# MC9S12C.net
KiCad netlist of a schematic drawn in Altium Designer
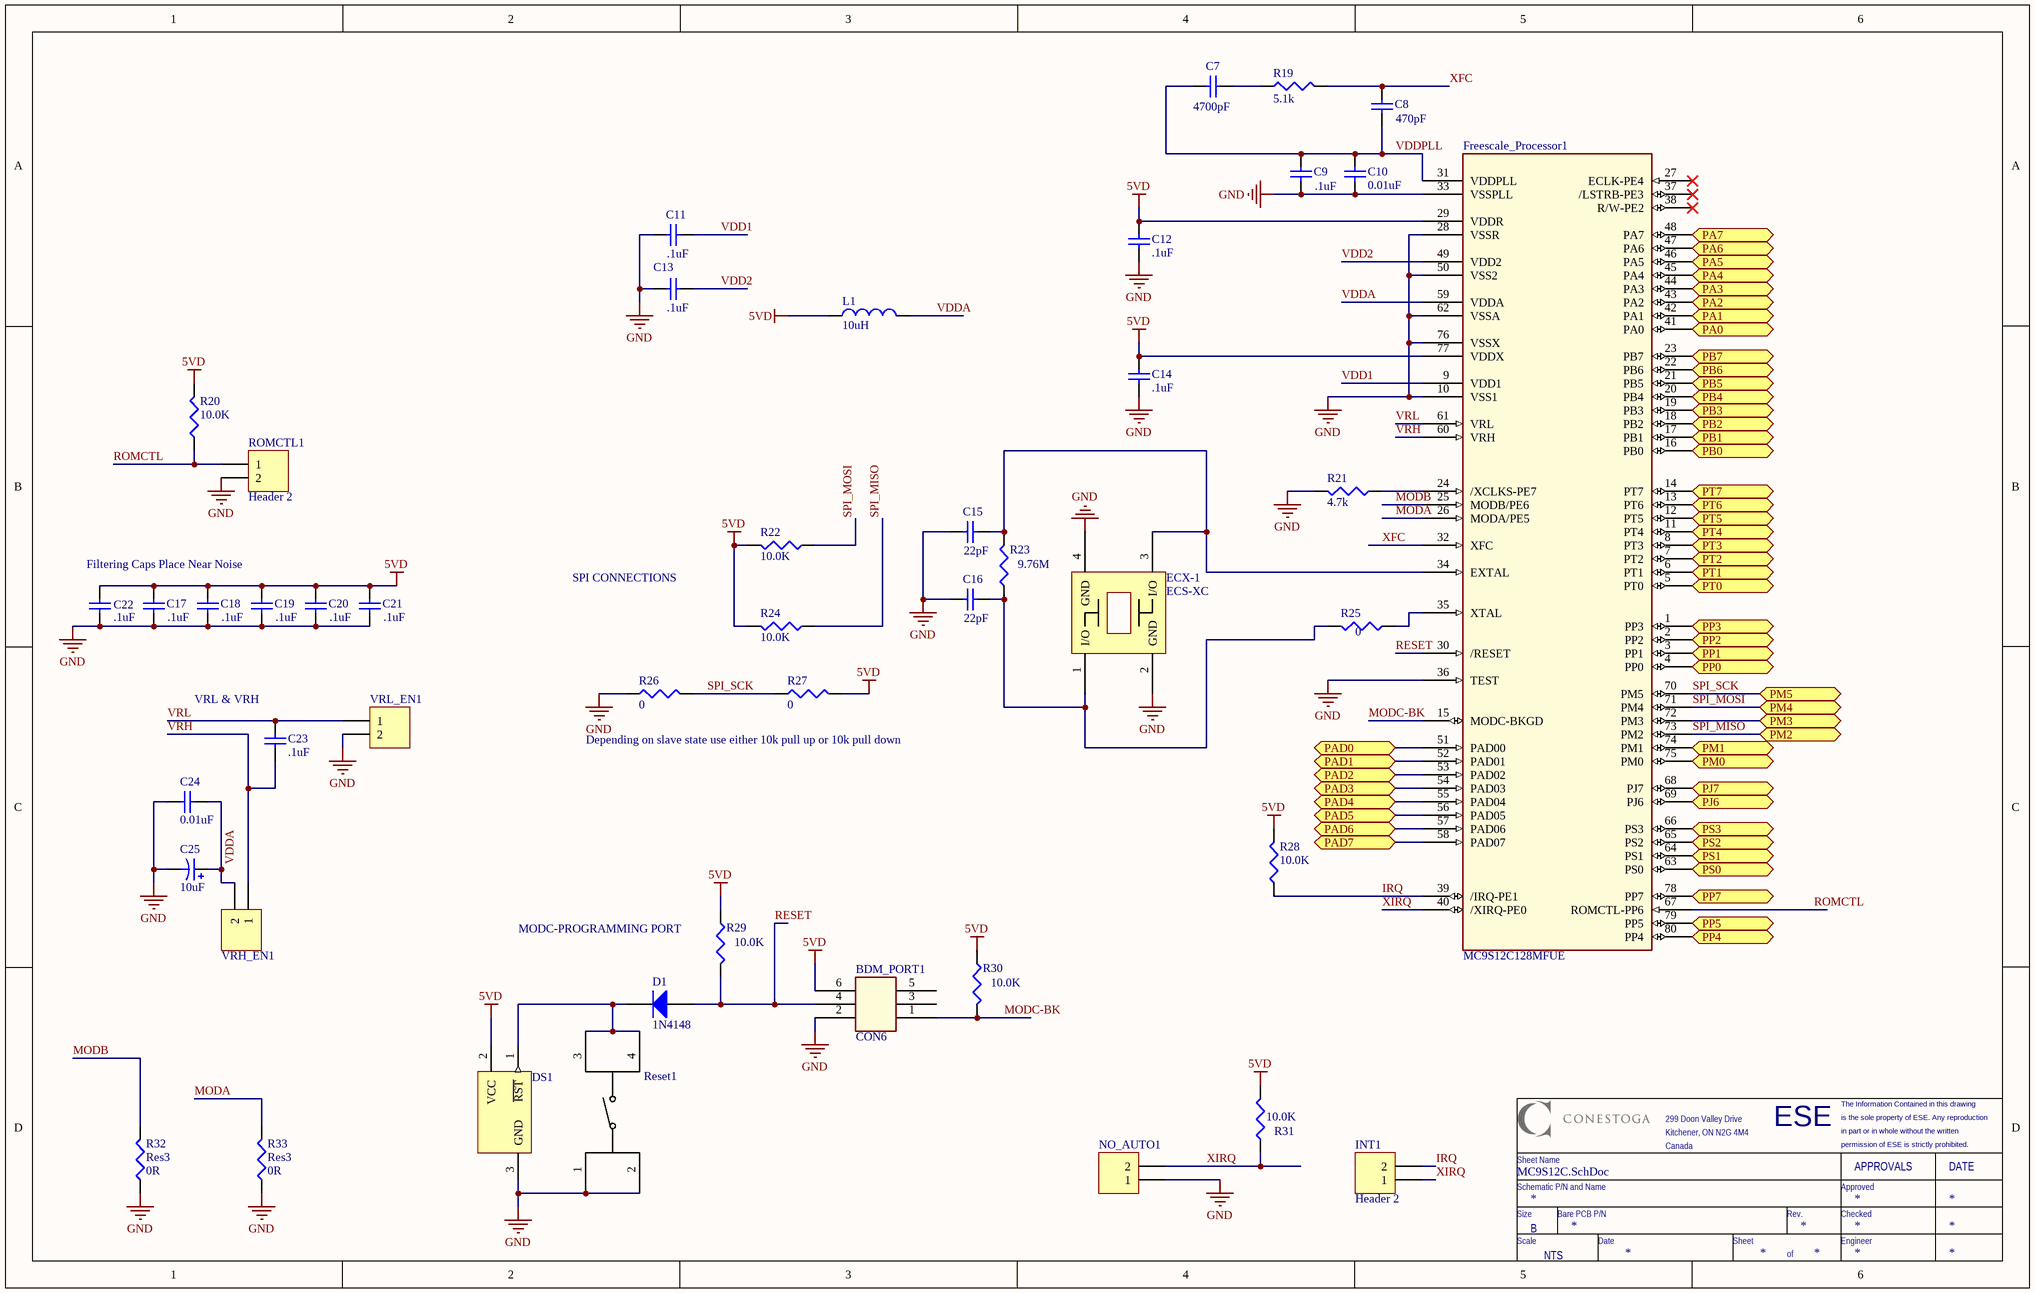
[diagram p0: MC9S12C.SchDoc]

(export (version "E")
  (design (tool "Eeschema 10.0.6"))
  (components
    (comp (ref "BDM_PORT1")
      (value "CON6")
      (footprint "HDR3X2")
      (description "CONN HEADER BRKWAY 6POS DL .100")
      (fields (field (name "MPN") "5-146254-3"))
      (libsource (lib "esd_library") (part "CON6"))
    )
    (comp (ref "C7")
      (value "4700pF")
      (footprint "CAPC2012X09M")
      (description "CAP CER 4700pF 50v X7R 0805")
      (fields (field (name "MPN") "C0805C472K5RACTU") (field (name "Comment") "p"))
      (libsource (lib "esd_library") (part "CAP-X7R-4700pF-50V-±10%"))
    )
    (comp (ref "C8")
      (value "470pF")
      (footprint "CAPC2012X09M")
      (description "CAP CER 470pF 50v X7R 0805")
      (fields (field (name "MPN") "C0805C471K5RACTU") (field (name "Comment") "ap"))
      (libsource (lib "esd_library") (part "CAP-X7R-470pF-50V-±10%"))
    )
    (comp (ref "C9")
      (value ".1uF")
      (footprint "CAPC2012X09M")
      (description "CAP CER .1uF 16v X7R 0805")
      (fields (field (name "MPN") "C0805C104K4RACTU") (field (name "Comment") "p"))
      (libsource (lib "esd_library") (part "CAP-X7R-.1uF-16V-±10%"))
    )
    (comp (ref "C10")
      (value "0.01uF")
      (footprint "C_805")
      (description "CAP CER 10000pF 50v Z5U 0805")
      (fields (field (name "MPN") "C0805C103Z5UACTU") (field (name "Comment") "Cap"))
      (libsource (lib "esd_library") (part "CAP-Z5U-10000pF-50V-+80%/-20%"))
    )
    (comp (ref "C11")
      (value ".1uF")
      (footprint "CAPC2012X09M")
      (description "CAP CER .1uF 16v X7R 0805")
      (fields (field (name "MPN") "C0805C104K4RACTU") (field (name "Comment") "Cap"))
      (libsource (lib "esd_library") (part "CAP-X7R-.1uF-16V-±10%"))
    )
    (comp (ref "C12")
      (value ".1uF")
      (footprint "C1206")
      (description "CAP CER .1uF 16v X7R 0805")
      (fields (field (name "MPN") "C0805C104K4RACTU") (field (name "Comment") "Cap"))
      (libsource (lib "esd_library") (part "CAP-X7R-.1uF-16V-±10%"))
    )
    (comp (ref "C13")
      (value ".1uF")
      (footprint "CAPC2012X09M")
      (description "CAP CER .1uF 16v X7R 0805")
      (fields (field (name "MPN") "C0805C104K4RACTU") (field (name "Comment") "Cap"))
      (libsource (lib "esd_library") (part "CAP-X7R-.1uF-16V-±10%"))
    )
    (comp (ref "C14")
      (value ".1uF")
      (footprint "C1206")
      (description "CAP CER .1uF 16v X7R 0805")
      (fields (field (name "MPN") "C0805C104K4RACTU") (field (name "Comment") "Cap"))
      (libsource (lib "esd_library") (part "CAP-X7R-.1uF-16V-±10%"))
    )
    (comp (ref "C15")
      (value "22pF")
      (footprint "CAPC2012X09M")
      (description "CAP CER 22pF 630v X7R 0805")
      (fields (field (name "MPN") "C0805C220KBRACTU") (field (name "Comment") "Cap"))
      (libsource (lib "esd_library") (part "CAP-X7R-22pF-630V-±10%"))
    )
    (comp (ref "C16")
      (value "22pF")
      (footprint "CAPC2012X09M")
      (description "CAP CER 22pF 630v X7R 0805")
      (fields (field (name "MPN") "C0805C220KBRACTU") (field (name "Comment") "Cap"))
      (libsource (lib "esd_library") (part "CAP-X7R-22pF-630V-±10%"))
    )
    (comp (ref "C17")
      (value ".1uF")
      (footprint "CAPC2012X09M")
      (description "CAP CER .1uF 50v X7R 0805")
      (fields (field (name "MPN") "C0805C104M5RACTU") (field (name "Comment") "Cap"))
      (libsource (lib "esd_library") (part "CAP-X7R-.1uF-50V-±20%"))
    )
    (comp (ref "C18")
      (value ".1uF")
      (footprint "CAPC2012X09M")
      (description "CAP CER .1uF 50v X7R 0805")
      (fields (field (name "MPN") "C0805C104M5RACTU") (field (name "Comment") "Cap"))
      (libsource (lib "esd_library") (part "CAP-X7R-.1uF-50V-±20%"))
    )
    (comp (ref "C19")
      (value ".1uF")
      (footprint "CAPC2012X09M")
      (description "CAP CER .1uF 50v X7R 0805")
      (fields (field (name "MPN") "C0805C104M5RACTU") (field (name "Comment") "Cap"))
      (libsource (lib "esd_library") (part "CAP-X7R-.1uF-50V-±20%"))
    )
    (comp (ref "C20")
      (value ".1uF")
      (footprint "CAPC2012X09M")
      (description "CAP CER .1uF 50v X7R 0805")
      (fields (field (name "MPN") "C0805C104M5RACTU") (field (name "Comment") "Cap"))
      (libsource (lib "esd_library") (part "CAP-X7R-.1uF-50V-±20%"))
    )
    (comp (ref "C21")
      (value ".1uF")
      (footprint "CAPC2012X09M")
      (description "CAP CER .1uF 50v X7R 0805")
      (fields (field (name "MPN") "C0805C104M5RACTU") (field (name "Comment") "Cap"))
      (libsource (lib "esd_library") (part "CAP-X7R-.1uF-50V-±20%"))
    )
    (comp (ref "C22")
      (value ".1uF")
      (footprint "CAPC2012X09M")
      (description "CAP CER .1uF 50v X7R 0805")
      (fields (field (name "MPN") "C0805C104M5RACTU") (field (name "Comment") "Cap"))
      (libsource (lib "esd_library") (part "CAP-X7R-.1uF-50V-±20%"))
    )
    (comp (ref "C23")
      (value ".1uF")
      (footprint "CAPC2012X09M")
      (description "CAP CER .1uF 16v X7R 0805")
      (fields (field (name "MPN") "C0805C104K4RACTU") (field (name "Comment") "Cap"))
      (libsource (lib "esd_library") (part "CAP-X7R-.1uF-16V-±10%"))
    )
    (comp (ref "C24")
      (value "0.01uF")
      (footprint "C_805")
      (description "CAP CER 10000pF 100v X7R 0805")
      (fields (field (name "MPN") "C0805C103K1RACTU") (field (name "Comment") "Cap"))
      (libsource (lib "esd_library") (part "CAP-X7R-10000pF-100V-±10%"))
    )
    (comp (ref "C25")
      (value "10uF")
      (footprint "CAPACITOR_3MM")
      (description "CAP 85C 10uF ±20% 16V WX Series Aluminum Electrolytic")
      (fields (field (name "MPN") "UWX1C100MCL2GB") (field (name "Comment") "Cap Pol"))
      (libsource (lib "esd_library") (part "Cap Polar-10uF-16V"))
    )
    (comp (ref "D1")
      (value "1N4148")
      (footprint "zener_sod323")
      (description "High Conductance Fast Diode")
      (fields (field (name "MPN") "1N4148WX-TP"))
      (libsource (lib "esd_library") (part "Diode 1N4148"))
    )
    (comp (ref "DS1")
      (value "DS1813-10")
      (footprint "SOT95P230X110-3M")
      (description "5V EconoReset with Pushbutton")
      (fields (field (name "MPN") "DS1813R-10+T&R") (field (name "PUBLISHER") "Altium Limited"))
      (libsource (lib "esd_library") (part "DS1813-10"))
    )
    (comp (ref "ECX-1") (value "ECS-XC") (footprint "ECX-32") (libsource (lib "Crystal") (part "ECS-XC")))
    (comp (ref "Freescale_Processor1")
      (value "MC9S12C128MFUE")
      (footprint "QUAD.65M/80/WG17.45-HCS12")
      (description "IC MCU 16BIT 128KB FLASH 80QFP")
      (fields (field (name "MPN") "MC9S12C32CFUE25"))
      (libsource (lib "esd_library") (part "MC9S12C128MFUE"))
    )
    (comp (ref "INT1")
      (value "Header 2")
      (footprint "HDR1X2")
      (description "Header, 2-Pin Male")
      (fields (field (name "MPN") "PEC02SFAN"))
      (libsource (lib "esd_library (1)") (part "Header 2"))
    )
    (comp (ref "L1")
      (value "10uH")
      (footprint "CAPC2012X09M")
      (libsource (lib "esd_library") (part "INDUCTOR"))
    )
    (comp (ref "NO_AUTO1")
      (value "Header 2")
      (footprint "HDR1X2")
      (description "Header, 2-Pin")
      (fields (field (name "MPN") "PEC02SFAN"))
      (libsource (lib "") (part "Header 2_1"))
    )
    (comp (ref "R19")
      (value "5.1k")
      (footprint "RESC2112X05M")
      (description "RES SMD 4.75K OHM 1% 1/8W 0805")
      (fields (field (name "MPN") "CRCW08054K75FKEA") (field (name "Comment") "Res3"))
      (libsource (lib "esd_library") (part "Resistor_4.75K"))
    )
    (comp (ref "R20")
      (value "10.0K")
      (footprint "RESC2112X05M")
      (description "RES SMD 10.0K OHM 1% 1/8W 0805")
      (fields (field (name "MPN") "CRCW080510K0FKEA") (field (name "Comment") "Res3"))
      (libsource (lib "esd_library") (part "Resistor_10.0K"))
    )
    (comp (ref "R21")
      (value "4.7k")
      (footprint "RESC2112X05M")
      (description "RES SMD 9.76M OHM 1% 1/8W 0805")
      (fields (field (name "MPN") "CRCW08059M76FKEA") (field (name "Comment") "Res3"))
      (libsource (lib "esd_library") (part "Resistor_9.76M"))
    )
    (comp (ref "R22")
      (value "10.0K")
      (footprint "RESC2112X05M")
      (description "RES SMD 10.0K OHM 1% 1/8W 0805")
      (fields (field (name "MPN") "CRCW080510K0FKEA") (field (name "Comment") "Res3"))
      (libsource (lib "esd_library") (part "Resistor_10.0K"))
    )
    (comp (ref "R23")
      (value "9.76M")
      (footprint "RESC2112X05M")
      (description "RES SMD 9.76M OHM 1% 1/8W 0805")
      (fields (field (name "MPN") "CRCW08059M76FKEA") (field (name "Comment") "Res3"))
      (libsource (lib "esd_library") (part "Resistor_9.76M"))
    )
    (comp (ref "R24")
      (value "10.0K")
      (footprint "RESC2112X05M")
      (description "RES SMD 10.0K OHM 1% 1/8W 0805")
      (fields (field (name "MPN") "CRCW080510K0FKEA") (field (name "Comment") "Res3"))
      (libsource (lib "esd_library") (part "Resistor_10.0K"))
    )
    (comp (ref "R25")
      (value "0")
      (footprint "RESC2112X05M")
      (description "RES SMD 9.76M OHM 1% 1/8W 0805")
      (fields (field (name "MPN") "CRCW08059M76FKEA") (field (name "Comment") "Res3"))
      (libsource (lib "esd_library") (part "Resistor_9.76M"))
    )
    (comp (ref "R26")
      (value "0")
      (footprint "RESC2112X05M")
      (description "RES SMD 1.00K OHM 1% 1/8W 0805")
      (fields (field (name "MPN") "CRCW08051K00FKEA") (field (name "Comment") "Res3"))
      (libsource (lib "esd_library") (part "Resistor_1.00K"))
    )
    (comp (ref "R27")
      (value "0")
      (footprint "RESC2112X05M")
      (description "RES SMD 1.00K OHM 1% 1/8W 0805")
      (fields (field (name "MPN") "CRCW08051K00FKEA") (field (name "Comment") "Res3"))
      (libsource (lib "esd_library") (part "Resistor_1.00K"))
    )
    (comp (ref "R28")
      (value "10.0K")
      (footprint "RESC2112X05M")
      (description "RES SMD 10.0K OHM 1% 1/8W 0805")
      (fields (field (name "MPN") "CRCW080510K0FKEA") (field (name "Comment") "Res3"))
      (libsource (lib "esd_library") (part "Resistor_10.0K"))
    )
    (comp (ref "R29")
      (value "10.0K")
      (footprint "RESC2112X05M")
      (description "RES SMD 10.0K OHM 1% 1/8W 0805")
      (fields (field (name "MPN") "CRCW080510K0FKEA") (field (name "Comment") "Res3"))
      (libsource (lib "esd_library") (part "Resistor_10.0K"))
    )
    (comp (ref "R30")
      (value "10.0K")
      (footprint "RESC2112X05M")
      (description "RES SMD 10.0K OHM 1% 1/8W 0805")
      (fields (field (name "MPN") "CRCW080510K0FKEA") (field (name "Comment") "Res3"))
      (libsource (lib "esd_library") (part "Resistor_10.0K"))
    )
    (comp (ref "R31")
      (value "10.0K")
      (footprint "RESC2112X05M")
      (description "RES SMD 10.0K OHM 1% 1/8W 0805")
      (fields (field (name "MPN") "CRCW080510K0FKEA") (field (name "Comment") "Res3"))
      (libsource (lib "esd_library") (part "Resistor_10.0K"))
    )
    (comp (ref "R32")
      (value "Res3")
      (footprint "RESC2112X05M")
      (description "RES SMD 0 OHM 5% 1/8W 0805")
      (fields (field (name "MPN") "CRCW08050000Z0EA") (field (name "ALTIUM_VALUE") "0R"))
      (libsource (lib "esd_library (1)") (part "Resistor_0R_Jumper"))
    )
    (comp (ref "R33")
      (value "Res3")
      (footprint "RESC2112X05M")
      (description "RES SMD 0 OHM 5% 1/8W 0805")
      (fields (field (name "MPN") "CRCW08050000Z0EA") (field (name "ALTIUM_VALUE") "0R"))
      (libsource (lib "esd_library (1)") (part "Resistor_0R_Jumper"))
    )
    (comp (ref "Reset1")
      (value "SWITCH_TACTILE")
      (footprint "TACT_SWITCH_6MM_SMT")
      (description "SWITCH TACTILE SPST-NO 0.05A 12V")
      (fields (field (name "MPN") "PTS645SH50SMTR92 LFS"))
      (libsource (lib "esd_library") (part "SWITCH_TACTILE"))
    )
    (comp (ref "ROMCTL1")
      (value "Header 2")
      (footprint "HDR1X2")
      (description "Header, 2-Pin")
      (fields (field (name "PUBLISHER") "Altium Limited"))
      (libsource (lib "Miscellaneous Connectors") (part "Header 2"))
    )
    (comp (ref "VRH_EN1")
      (value "Header 2")
      (footprint "HDR1X2")
      (description "Header, 2-Pin")
      (fields (field (name "MPN") "PEC02SFAN"))
      (libsource (lib "") (part "Header 2_2"))
    )
    (comp (ref "VRL_EN1")
      (value "Header 2")
      (footprint "HDR1X2")
      (description "Header, 2-Pin")
      (fields (field (name "MPN") "PEC02SFAN"))
      (libsource (lib "esd_library") (part "Header 2"))
    )
  )
  (nets
    (net (code "1") (name "/IRQ") (class "Default")
      (node (ref "Freescale_Processor1") (pin "39") (pinfunction "/IRQ-PE1_39") (pintype "bidirectional"))
      (node (ref "INT1") (pin "2") (pinfunction "2_2") (pintype "passive"))
      (node (ref "R28") (pin "1") (pinfunction "1_1") (pintype "passive"))
    )
    (net (code "2") (name "/MODA") (class "Default")
      (node (ref "Freescale_Processor1") (pin "26") (pinfunction "MODA/PE5_26") (pintype "input"))
      (node (ref "R33") (pin "2") (pinfunction "2_2") (pintype "passive"))
    )
    (net (code "3") (name "/MODB") (class "Default")
      (node (ref "Freescale_Processor1") (pin "25") (pinfunction "MODB/PE6_25") (pintype "input"))
      (node (ref "R32") (pin "2") (pinfunction "2_2") (pintype "passive"))
    )
    (net (code "4") (name "/MODC-BK") (class "Default")
      (node (ref "BDM_PORT1") (pin "1") (pinfunction "1_1") (pintype "passive"))
      (node (ref "Freescale_Processor1") (pin "15") (pinfunction "MODC-BKGD_15") (pintype "bidirectional"))
      (node (ref "R30") (pin "2") (pinfunction "2_2") (pintype "passive"))
    )
    (net (code "5") (name "/PA0") (class "Default")
      (node (ref "Freescale_Processor1") (pin "41") (pinfunction "PA0_41") (pintype "bidirectional"))
    )
    (net (code "6") (name "/PA1") (class "Default")
      (node (ref "Freescale_Processor1") (pin "42") (pinfunction "PA1_42") (pintype "bidirectional"))
    )
    (net (code "7") (name "/PA2") (class "Default")
      (node (ref "Freescale_Processor1") (pin "43") (pinfunction "PA2_43") (pintype "bidirectional"))
    )
    (net (code "8") (name "/PA3") (class "Default")
      (node (ref "Freescale_Processor1") (pin "44") (pinfunction "PA3_44") (pintype "bidirectional"))
    )
    (net (code "9") (name "/PA4") (class "Default")
      (node (ref "Freescale_Processor1") (pin "45") (pinfunction "PA4_45") (pintype "bidirectional"))
    )
    (net (code "10") (name "/PA5") (class "Default")
      (node (ref "Freescale_Processor1") (pin "46") (pinfunction "PA5_46") (pintype "bidirectional"))
    )
    (net (code "11") (name "/PA6") (class "Default")
      (node (ref "Freescale_Processor1") (pin "47") (pinfunction "PA6_47") (pintype "bidirectional"))
    )
    (net (code "12") (name "/PA7") (class "Default")
      (node (ref "Freescale_Processor1") (pin "48") (pinfunction "PA7_48") (pintype "bidirectional"))
    )
    (net (code "13") (name "/PAD0") (class "Default")
      (node (ref "Freescale_Processor1") (pin "51") (pinfunction "PAD00_51") (pintype "input"))
    )
    (net (code "14") (name "/PAD1") (class "Default")
      (node (ref "Freescale_Processor1") (pin "52") (pinfunction "PAD01_52") (pintype "input"))
    )
    (net (code "15") (name "/PAD2") (class "Default")
      (node (ref "Freescale_Processor1") (pin "53") (pinfunction "PAD02_53") (pintype "input"))
    )
    (net (code "16") (name "/PAD3") (class "Default")
      (node (ref "Freescale_Processor1") (pin "54") (pinfunction "PAD03_54") (pintype "input"))
    )
    (net (code "17") (name "/PAD4") (class "Default")
      (node (ref "Freescale_Processor1") (pin "55") (pinfunction "PAD04_55") (pintype "input"))
    )
    (net (code "18") (name "/PAD5") (class "Default")
      (node (ref "Freescale_Processor1") (pin "56") (pinfunction "PAD05_56") (pintype "input"))
    )
    (net (code "19") (name "/PAD6") (class "Default")
      (node (ref "Freescale_Processor1") (pin "57") (pinfunction "PAD06_57") (pintype "input"))
    )
    (net (code "20") (name "/PAD7") (class "Default")
      (node (ref "Freescale_Processor1") (pin "58") (pinfunction "PAD07_58") (pintype "input"))
    )
    (net (code "21") (name "/PB0") (class "Default")
      (node (ref "Freescale_Processor1") (pin "16") (pinfunction "PB0_16") (pintype "bidirectional"))
    )
    (net (code "22") (name "/PB1") (class "Default")
      (node (ref "Freescale_Processor1") (pin "17") (pinfunction "PB1_17") (pintype "bidirectional"))
    )
    (net (code "23") (name "/PB2") (class "Default")
      (node (ref "Freescale_Processor1") (pin "18") (pinfunction "PB2_18") (pintype "bidirectional"))
    )
    (net (code "24") (name "/PB3") (class "Default")
      (node (ref "Freescale_Processor1") (pin "19") (pinfunction "PB3_19") (pintype "bidirectional"))
    )
    (net (code "25") (name "/PB4") (class "Default")
      (node (ref "Freescale_Processor1") (pin "20") (pinfunction "PB4_20") (pintype "bidirectional"))
    )
    (net (code "26") (name "/PB5") (class "Default")
      (node (ref "Freescale_Processor1") (pin "21") (pinfunction "PB5_21") (pintype "bidirectional"))
    )
    (net (code "27") (name "/PB6") (class "Default")
      (node (ref "Freescale_Processor1") (pin "22") (pinfunction "PB6_22") (pintype "bidirectional"))
    )
    (net (code "28") (name "/PB7") (class "Default")
      (node (ref "Freescale_Processor1") (pin "23") (pinfunction "PB7_23") (pintype "bidirectional"))
    )
    (net (code "29") (name "/PJ6") (class "Default")
      (node (ref "Freescale_Processor1") (pin "69") (pinfunction "PJ6_69") (pintype "bidirectional"))
    )
    (net (code "30") (name "/PJ7") (class "Default")
      (node (ref "Freescale_Processor1") (pin "68") (pinfunction "PJ7_68") (pintype "bidirectional"))
    )
    (net (code "31") (name "/PM0") (class "Default")
      (node (ref "Freescale_Processor1") (pin "75") (pinfunction "PM0_75") (pintype "bidirectional"))
    )
    (net (code "32") (name "/PM1") (class "Default")
      (node (ref "Freescale_Processor1") (pin "74") (pinfunction "PM1_74") (pintype "bidirectional"))
    )
    (net (code "33") (name "/PM3") (class "Default")
      (node (ref "Freescale_Processor1") (pin "72") (pinfunction "PM3_72") (pintype "bidirectional"))
    )
    (net (code "34") (name "/PP0") (class "Default")
      (node (ref "Freescale_Processor1") (pin "4") (pinfunction "PP0_4") (pintype "bidirectional"))
    )
    (net (code "35") (name "/PP1") (class "Default")
      (node (ref "Freescale_Processor1") (pin "3") (pinfunction "PP1_3") (pintype "bidirectional"))
    )
    (net (code "36") (name "/PP2") (class "Default")
      (node (ref "Freescale_Processor1") (pin "2") (pinfunction "PP2_2") (pintype "bidirectional"))
    )
    (net (code "37") (name "/PP3") (class "Default")
      (node (ref "Freescale_Processor1") (pin "1") (pinfunction "PP3_1") (pintype "bidirectional"))
    )
    (net (code "38") (name "/PP4") (class "Default")
      (node (ref "Freescale_Processor1") (pin "80") (pinfunction "PP4_80") (pintype "bidirectional"))
    )
    (net (code "39") (name "/PP5") (class "Default")
      (node (ref "Freescale_Processor1") (pin "79") (pinfunction "PP5_79") (pintype "bidirectional"))
    )
    (net (code "40") (name "/PP7") (class "Default")
      (node (ref "Freescale_Processor1") (pin "78") (pinfunction "PP7_78") (pintype "bidirectional"))
    )
    (net (code "41") (name "/PS0") (class "Default")
      (node (ref "Freescale_Processor1") (pin "63") (pinfunction "PS0_63") (pintype "bidirectional"))
    )
    (net (code "42") (name "/PS1") (class "Default")
      (node (ref "Freescale_Processor1") (pin "64") (pinfunction "PS1_64") (pintype "bidirectional"))
    )
    (net (code "43") (name "/PS2") (class "Default")
      (node (ref "Freescale_Processor1") (pin "65") (pinfunction "PS2_65") (pintype "bidirectional"))
    )
    (net (code "44") (name "/PS3") (class "Default")
      (node (ref "Freescale_Processor1") (pin "66") (pinfunction "PS3_66") (pintype "bidirectional"))
    )
    (net (code "45") (name "/PT0") (class "Default")
      (node (ref "Freescale_Processor1") (pin "5") (pinfunction "PT0_5") (pintype "bidirectional"))
    )
    (net (code "46") (name "/PT1") (class "Default")
      (node (ref "Freescale_Processor1") (pin "6") (pinfunction "PT1_6") (pintype "bidirectional"))
    )
    (net (code "47") (name "/PT2") (class "Default")
      (node (ref "Freescale_Processor1") (pin "7") (pinfunction "PT2_7") (pintype "bidirectional"))
    )
    (net (code "48") (name "/PT3") (class "Default")
      (node (ref "Freescale_Processor1") (pin "8") (pinfunction "PT3_8") (pintype "bidirectional"))
    )
    (net (code "49") (name "/PT4") (class "Default")
      (node (ref "Freescale_Processor1") (pin "11") (pinfunction "PT4_11") (pintype "bidirectional"))
    )
    (net (code "50") (name "/PT5") (class "Default")
      (node (ref "Freescale_Processor1") (pin "12") (pinfunction "PT5_12") (pintype "bidirectional"))
    )
    (net (code "51") (name "/PT6") (class "Default")
      (node (ref "Freescale_Processor1") (pin "13") (pinfunction "PT6_13") (pintype "bidirectional"))
    )
    (net (code "52") (name "/PT7") (class "Default")
      (node (ref "Freescale_Processor1") (pin "14") (pinfunction "PT7_14") (pintype "bidirectional"))
    )
    (net (code "53") (name "/RESET") (class "Default")
      (node (ref "BDM_PORT1") (pin "4") (pinfunction "4_4") (pintype "passive"))
      (node (ref "D1") (pin "A") (pinfunction "A_A") (pintype "passive"))
      (node (ref "Freescale_Processor1") (pin "30") (pinfunction "/RESET_30") (pintype "input"))
      (node (ref "R29") (pin "2") (pinfunction "2_2") (pintype "passive"))
    )
    (net (code "54") (name "/ROMCTL") (class "Default")
      (node (ref "Freescale_Processor1") (pin "67") (pinfunction "ROMCTL-PP6_67") (pintype "input"))
      (node (ref "R20") (pin "1") (pinfunction "1_1") (pintype "passive"))
      (node (ref "ROMCTL1") (pin "1") (pinfunction "1_1") (pintype "passive"))
    )
    (net (code "55") (name "/SPI_MISO") (class "Default")
      (node (ref "Freescale_Processor1") (pin "73") (pinfunction "PM2_73") (pintype "bidirectional"))
      (node (ref "R24") (pin "1") (pinfunction "1_1") (pintype "passive"))
    )
    (net (code "56") (name "/SPI_MOSI") (class "Default")
      (node (ref "Freescale_Processor1") (pin "71") (pinfunction "PM4_71") (pintype "bidirectional"))
      (node (ref "R22") (pin "1") (pinfunction "1_1") (pintype "passive"))
    )
    (net (code "57") (name "/SPI_SCK") (class "Default")
      (node (ref "Freescale_Processor1") (pin "70") (pinfunction "PM5_70") (pintype "bidirectional"))
      (node (ref "R26") (pin "2") (pinfunction "2_2") (pintype "passive"))
      (node (ref "R27") (pin "1") (pinfunction "1_1") (pintype "passive"))
    )
    (net (code "58") (name "/VDD1") (class "Default")
      (node (ref "C11") (pin "2") (pinfunction "2_2") (pintype "passive"))
      (node (ref "Freescale_Processor1") (pin "9") (pinfunction "VDD1_9") (pintype "power_in"))
    )
    (net (code "59") (name "/VDD2") (class "Default")
      (node (ref "C13") (pin "2") (pinfunction "2_2") (pintype "passive"))
      (node (ref "Freescale_Processor1") (pin "49") (pinfunction "VDD2_49") (pintype "power_in"))
    )
    (net (code "60") (name "/VDDA") (class "Default")
      (node (ref "C24") (pin "2") (pinfunction "2_2") (pintype "passive"))
      (node (ref "C25") (pin "1") (pinfunction "1_1") (pintype "passive"))
      (node (ref "Freescale_Processor1") (pin "59") (pinfunction "VDDA_59") (pintype "power_in"))
      (node (ref "L1") (pin "2") (pinfunction "2_2") (pintype "passive"))
      (node (ref "VRH_EN1") (pin "2") (pinfunction "2_2") (pintype "passive"))
    )
    (net (code "61") (name "/VDDPLL") (class "Default")
      (node (ref "C10") (pin "2") (pinfunction "2_2") (pintype "passive"))
      (node (ref "C7") (pin "1") (pinfunction "1_1") (pintype "passive"))
      (node (ref "C8") (pin "1") (pinfunction "1_1") (pintype "passive"))
      (node (ref "C9") (pin "2") (pinfunction "2_2") (pintype "passive"))
      (node (ref "Freescale_Processor1") (pin "31") (pinfunction "VDDPLL_31") (pintype "power_in"))
    )
    (net (code "62") (name "/VRH") (class "Default")
      (node (ref "C23") (pin "2") (pinfunction "2_2") (pintype "passive"))
      (node (ref "Freescale_Processor1") (pin "60") (pinfunction "VRH_60") (pintype "input"))
      (node (ref "VRH_EN1") (pin "1") (pinfunction "1_1") (pintype "passive"))
    )
    (net (code "63") (name "/VRL") (class "Default")
      (node (ref "C23") (pin "1") (pinfunction "1_1") (pintype "passive"))
      (node (ref "Freescale_Processor1") (pin "61") (pinfunction "VRL_61") (pintype "input"))
      (node (ref "VRL_EN1") (pin "1") (pinfunction "1_1") (pintype "passive"))
    )
    (net (code "64") (name "/XFC") (class "Default")
      (node (ref "C8") (pin "2") (pinfunction "2_2") (pintype "passive"))
      (node (ref "Freescale_Processor1") (pin "32") (pinfunction "XFC_32") (pintype "input"))
      (node (ref "R19") (pin "2") (pinfunction "2_2") (pintype "passive"))
    )
    (net (code "65") (name "/XIRQ") (class "Default")
      (node (ref "Freescale_Processor1") (pin "40") (pinfunction "/XIRQ-PE0_40") (pintype "bidirectional"))
      (node (ref "INT1") (pin "1") (pinfunction "1_1") (pintype "passive"))
      (node (ref "NO_AUTO1") (pin "2") (pinfunction "2_2") (pintype "passive"))
      (node (ref "R31") (pin "1") (pinfunction "1_1") (pintype "passive"))
    )
    (net (code "66") (name "5VD") (class "Default")
      (node (ref "BDM_PORT1") (pin "6") (pinfunction "6_6") (pintype "passive"))
      (node (ref "C12") (pin "2") (pinfunction "2_2") (pintype "passive"))
      (node (ref "C14") (pin "2") (pinfunction "2_2") (pintype "passive"))
      (node (ref "C17") (pin "2") (pinfunction "2_2") (pintype "passive"))
      (node (ref "C18") (pin "2") (pinfunction "2_2") (pintype "passive"))
      (node (ref "C19") (pin "2") (pinfunction "2_2") (pintype "passive"))
      (node (ref "C20") (pin "2") (pinfunction "2_2") (pintype "passive"))
      (node (ref "C21") (pin "2") (pinfunction "2_2") (pintype "passive"))
      (node (ref "C22") (pin "2") (pinfunction "2_2") (pintype "passive"))
      (node (ref "DS1") (pin "2") (pinfunction "VCC_2") (pintype "power_in"))
      (node (ref "Freescale_Processor1") (pin "29") (pinfunction "VDDR_29") (pintype "power_in"))
      (node (ref "Freescale_Processor1") (pin "77") (pinfunction "VDDX_77") (pintype "power_in"))
      (node (ref "L1") (pin "1") (pinfunction "1_1") (pintype "passive"))
      (node (ref "R20") (pin "2") (pinfunction "2_2") (pintype "passive"))
      (node (ref "R22") (pin "2") (pinfunction "2_2") (pintype "passive"))
      (node (ref "R24") (pin "2") (pinfunction "2_2") (pintype "passive"))
      (node (ref "R27") (pin "2") (pinfunction "2_2") (pintype "passive"))
      (node (ref "R28") (pin "2") (pinfunction "2_2") (pintype "passive"))
      (node (ref "R29") (pin "1") (pinfunction "1_1") (pintype "passive"))
      (node (ref "R30") (pin "1") (pinfunction "1_1") (pintype "passive"))
      (node (ref "R31") (pin "2") (pinfunction "2_2") (pintype "passive"))
    )
    (net (code "67") (name "GND") (class "Default")
      (node (ref "BDM_PORT1") (pin "2") (pinfunction "2_2") (pintype "passive"))
      (node (ref "C10") (pin "1") (pinfunction "1_1") (pintype "passive"))
      (node (ref "C11") (pin "1") (pinfunction "1_1") (pintype "passive"))
      (node (ref "C12") (pin "1") (pinfunction "1_1") (pintype "passive"))
      (node (ref "C13") (pin "1") (pinfunction "1_1") (pintype "passive"))
      (node (ref "C14") (pin "1") (pinfunction "1_1") (pintype "passive"))
      (node (ref "C15") (pin "1") (pinfunction "1_1") (pintype "passive"))
      (node (ref "C16") (pin "1") (pinfunction "1_1") (pintype "passive"))
      (node (ref "C17") (pin "1") (pinfunction "1_1") (pintype "passive"))
      (node (ref "C18") (pin "1") (pinfunction "1_1") (pintype "passive"))
      (node (ref "C19") (pin "1") (pinfunction "1_1") (pintype "passive"))
      (node (ref "C20") (pin "1") (pinfunction "1_1") (pintype "passive"))
      (node (ref "C21") (pin "1") (pinfunction "1_1") (pintype "passive"))
      (node (ref "C22") (pin "1") (pinfunction "1_1") (pintype "passive"))
      (node (ref "C24") (pin "1") (pinfunction "1_1") (pintype "passive"))
      (node (ref "C25") (pin "2") (pinfunction "2_2") (pintype "passive"))
      (node (ref "C9") (pin "1") (pinfunction "1_1") (pintype "passive"))
      (node (ref "DS1") (pin "3") (pinfunction "GND_3") (pintype "power_in"))
      (node (ref "ECX-1") (pin "2") (pinfunction "GND_2") (pintype "passive"))
      (node (ref "ECX-1") (pin "4") (pinfunction "GND_4") (pintype "passive"))
      (node (ref "Freescale_Processor1") (pin "10") (pinfunction "VSS1_10") (pintype "power_in"))
      (node (ref "Freescale_Processor1") (pin "28") (pinfunction "VSSR_28") (pintype "power_in"))
      (node (ref "Freescale_Processor1") (pin "33") (pinfunction "VSSPLL_33") (pintype "power_in"))
      (node (ref "Freescale_Processor1") (pin "36") (pinfunction "TEST_36") (pintype "input"))
      (node (ref "Freescale_Processor1") (pin "50") (pinfunction "VSS2_50") (pintype "power_in"))
      (node (ref "Freescale_Processor1") (pin "62") (pinfunction "VSSA_62") (pintype "power_in"))
      (node (ref "Freescale_Processor1") (pin "76") (pinfunction "VSSX_76") (pintype "power_in"))
      (node (ref "NO_AUTO1") (pin "1") (pinfunction "1_1") (pintype "passive"))
      (node (ref "R21") (pin "2") (pinfunction "2_2") (pintype "passive"))
      (node (ref "R26") (pin "1") (pinfunction "1_1") (pintype "passive"))
      (node (ref "R32") (pin "1") (pinfunction "1_1") (pintype "passive"))
      (node (ref "R33") (pin "1") (pinfunction "1_1") (pintype "passive"))
      (node (ref "ROMCTL1") (pin "2") (pinfunction "2_2") (pintype "passive"))
      (node (ref "Reset1") (pin "1") (pinfunction "1_1") (pintype "passive"))
      (node (ref "Reset1") (pin "2") (pinfunction "2_2") (pintype "passive"))
      (node (ref "VRL_EN1") (pin "2") (pinfunction "2_2") (pintype "passive"))
    )
    (net (code "68") (name "Net-(C7-Pad2)") (class "Default")
      (node (ref "C7") (pin "2") (pinfunction "2_2") (pintype "passive"))
      (node (ref "R19") (pin "1") (pinfunction "1_1") (pintype "passive"))
    )
    (net (code "69") (name "Net-(C16-Pad2)") (class "Default")
      (node (ref "C16") (pin "2") (pinfunction "2_2") (pintype "passive"))
      (node (ref "ECX-1") (pin "1") (pinfunction "I/O_1") (pintype "passive"))
      (node (ref "R23") (pin "1") (pinfunction "1_1") (pintype "passive"))
      (node (ref "R25") (pin "2") (pinfunction "2_2") (pintype "passive"))
    )
    (net (code "70") (name "Net-(DS1-~{RST})") (class "Default")
      (node (ref "D1") (pin "K") (pinfunction "K_K") (pintype "passive"))
      (node (ref "DS1") (pin "1") (pinfunction "~{RST}_1") (pintype "output"))
      (node (ref "Reset1") (pin "3") (pinfunction "3_3") (pintype "passive"))
      (node (ref "Reset1") (pin "4") (pinfunction "4_4") (pintype "passive"))
    )
    (net (code "71") (name "Net-(Freescale_Processor1-EXTAL)") (class "Default")
      (node (ref "C15") (pin "2") (pinfunction "2_2") (pintype "passive"))
      (node (ref "ECX-1") (pin "3") (pinfunction "I/O_3") (pintype "passive"))
      (node (ref "Freescale_Processor1") (pin "34") (pinfunction "EXTAL_34") (pintype "input"))
      (node (ref "R23") (pin "2") (pinfunction "2_2") (pintype "passive"))
    )
    (net (code "72") (name "Net-(Freescale_Processor1-XTAL)") (class "Default")
      (node (ref "Freescale_Processor1") (pin "35") (pinfunction "XTAL_35") (pintype "input"))
      (node (ref "R25") (pin "1") (pinfunction "1_1") (pintype "passive"))
    )
    (net (code "73") (name "Net-(Freescale_Processor1-{slash}XCLKS-PE7)") (class "Default")
      (node (ref "Freescale_Processor1") (pin "24") (pinfunction "/XCLKS-PE7_24") (pintype "input"))
      (node (ref "R21") (pin "1") (pinfunction "1_1") (pintype "passive"))
    )
    (net (code "74") (name "unconnected-(BDM_PORT1-Pad3)") (class "Default")
      (node (ref "BDM_PORT1") (pin "3") (pinfunction "3_3") (pintype "passive"))
    )
    (net (code "75") (name "unconnected-(BDM_PORT1-Pad5)") (class "Default")
      (node (ref "BDM_PORT1") (pin "5") (pinfunction "5_5") (pintype "passive"))
    )
    (net (code "76") (name "unconnected-(Freescale_Processor1-ECLK-PE4-Pad27)") (class "Default")
      (node (ref "Freescale_Processor1") (pin "27") (pinfunction "ECLK-PE4_27") (pintype "input+no_connect"))
    )
    (net (code "77") (name "unconnected-(Freescale_Processor1-R{slash}W-PE2-Pad38)") (class "Default")
      (node (ref "Freescale_Processor1") (pin "38") (pinfunction "R/W-PE2_38") (pintype "bidirectional+no_connect"))
    )
    (net (code "78") (name "unconnected-(Freescale_Processor1-{slash}LSTRB-PE3-Pad37)") (class "Default")
      (node (ref "Freescale_Processor1") (pin "37") (pinfunction "/LSTRB-PE3_37") (pintype "bidirectional+no_connect"))
    )
  )
)
